# main_V2.net
KiCad netlist of a schematic drawn in EAGLE
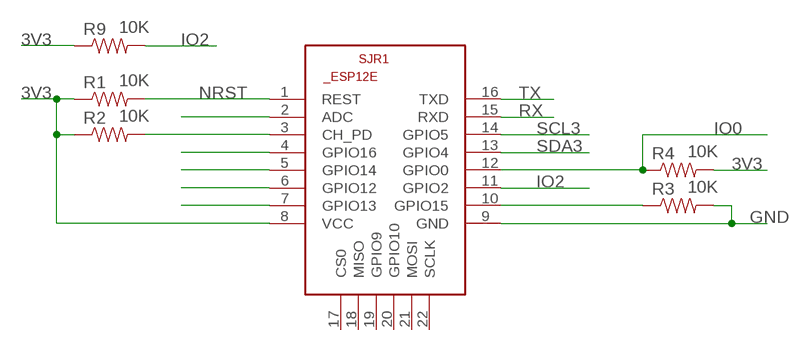
[diagram p0: schematic, sheet 1]
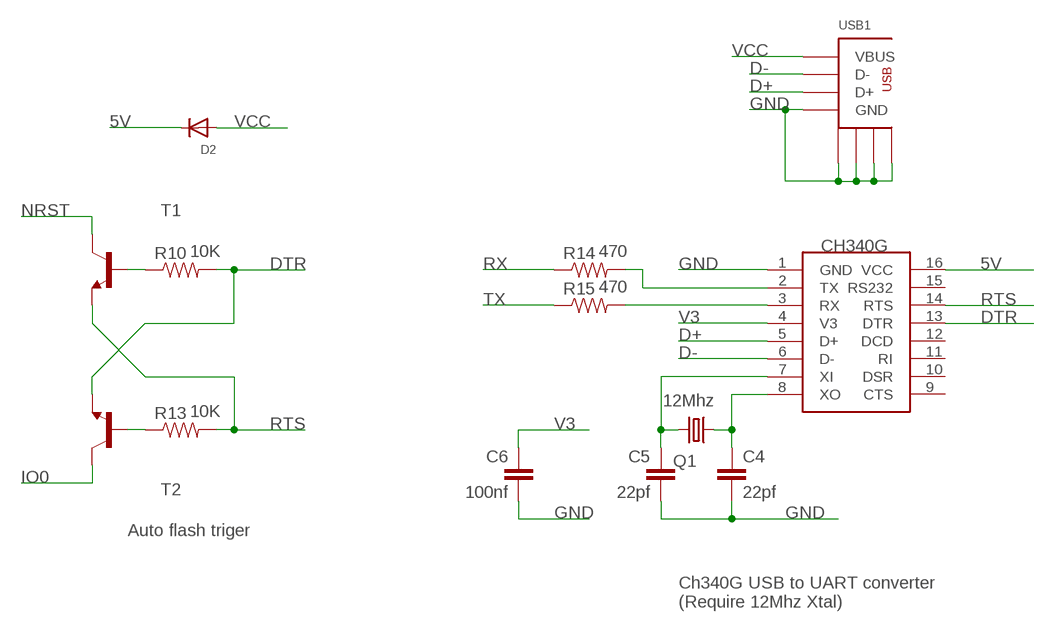
[diagram p1: schematic, sheet 2]
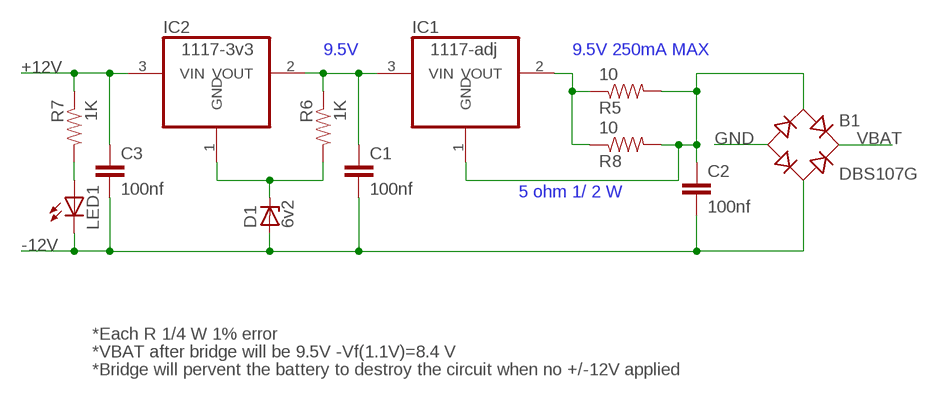
[diagram p2: schematic, sheet 3]
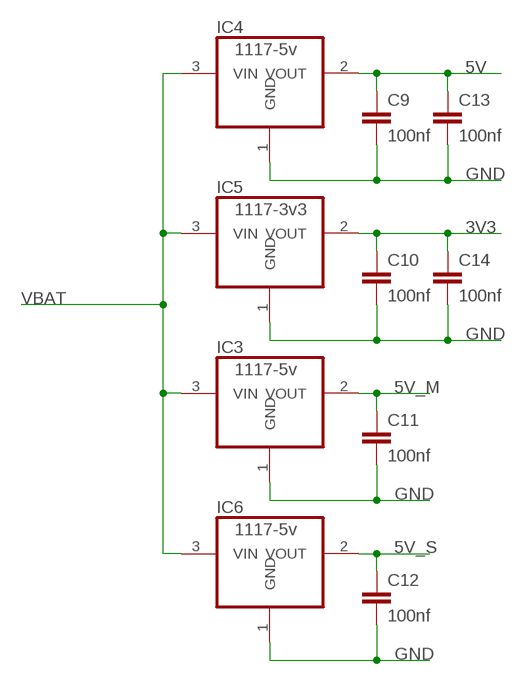
[diagram p3: schematic, sheet 4]
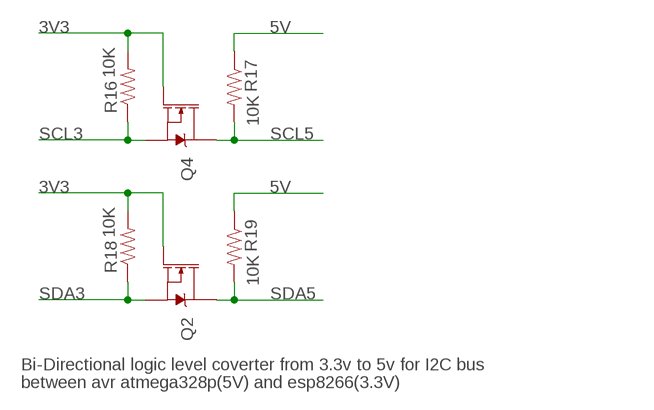
[diagram p4: schematic, sheet 5]
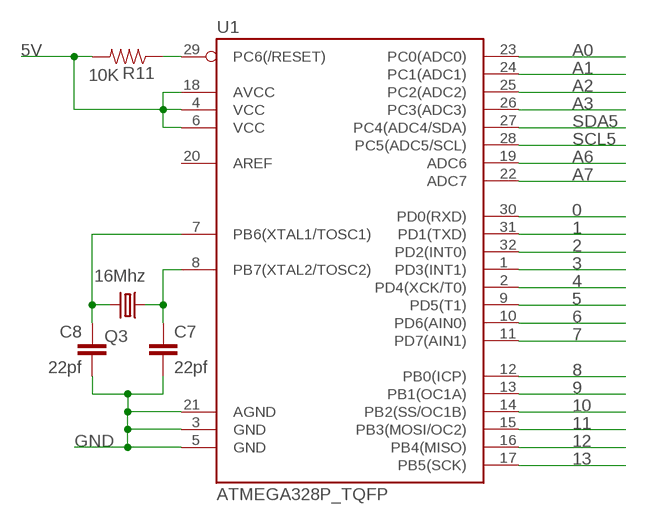
[diagram p5: schematic, sheet 6]
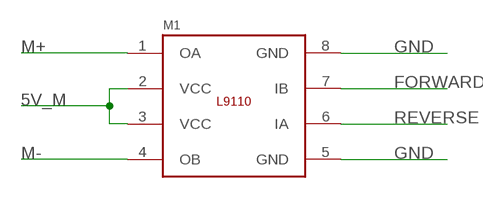
[diagram p6: schematic, sheet 7]

(export (version "E")
  (design (tool "Eeschema 10.0.6"))
  (components
    (comp (ref "C9")
      (value "100nf")
      (footprint "eagle-import:C1206K")
      (libsource (lib "eagle-import") (part "C-EUC1206K"))
    )
    (comp (ref "C10")
      (value "100nf")
      (footprint "eagle-import:C1206K")
      (libsource (lib "eagle-import") (part "C-EUC1206K"))
    )
    (comp (ref "C11")
      (value "100nf")
      (footprint "eagle-import:C1206K")
      (libsource (lib "eagle-import") (part "C-EUC1206K"))
    )
    (comp (ref "C12")
      (value "100nf")
      (footprint "eagle-import:C1206K")
      (libsource (lib "eagle-import") (part "C-EUC1206K"))
    )
    (comp (ref "C13")
      (value "100nf")
      (footprint "eagle-import:C1206K")
      (libsource (lib "eagle-import") (part "C-EUC1206K"))
    )
    (comp (ref "C14")
      (value "100nf")
      (footprint "eagle-import:C1206K")
      (libsource (lib "eagle-import") (part "C-EUC1206K"))
    )
    (comp (ref "IC3")
      (value "1117-5v")
      (footprint "eagle-import:SOT223")
      (fields (field (name "MPN") "REG1117"))
      (libsource (lib "eagle-import") (part "REG1117"))
    )
    (comp (ref "IC4")
      (value "1117-5v")
      (footprint "eagle-import:SOT223")
      (fields (field (name "MPN") "REG1117"))
      (libsource (lib "eagle-import") (part "REG1117"))
    )
    (comp (ref "IC5")
      (value "1117-3v3")
      (footprint "eagle-import:SOT223")
      (fields (field (name "MPN") "REG1117"))
      (libsource (lib "eagle-import") (part "REG1117"))
    )
    (comp (ref "IC6")
      (value "1117-5v")
      (footprint "eagle-import:SOT223")
      (fields (field (name "MPN") "REG1117"))
      (libsource (lib "eagle-import") (part "REG1117"))
    )
    (comp (ref "B1")
      (value "DBS107G")
      (footprint "eagle-import:DBS")
      (libsource (lib "eagle-import") (part "DB?GS107"))
    )
    (comp (ref "C1")
      (value "100nf")
      (footprint "eagle-import:C1206K")
      (libsource (lib "eagle-import") (part "C-EUC1206K"))
    )
    (comp (ref "C2")
      (value "100nf")
      (footprint "eagle-import:C1206K")
      (libsource (lib "eagle-import") (part "C-EUC1206K"))
    )
    (comp (ref "C3")
      (value "100nf")
      (footprint "eagle-import:C1206K")
      (libsource (lib "eagle-import") (part "C-EUC1206K"))
    )
    (comp (ref "D1")
      (value "6v2")
      (footprint "eagle-import:SOT23")
      (libsource (lib "eagle-import") (part "ZENER-DIODESOT23"))
    )
    (comp (ref "IC1")
      (value "1117-adj")
      (footprint "eagle-import:SOT223")
      (fields (field (name "MPN") "REG1117"))
      (libsource (lib "eagle-import") (part "REG1117"))
    )
    (comp (ref "IC2")
      (value "1117-3v3")
      (footprint "eagle-import:SOT223")
      (fields (field (name "MPN") "REG1117"))
      (libsource (lib "eagle-import") (part "REG1117"))
    )
    (comp (ref "LED1")
      (value "LEDSMT1206")
      (footprint "eagle-import:1206")
      (libsource (lib "eagle-import") (part "LEDSMT1206"))
    )
    (comp (ref "R5")
      (value "10")
      (footprint "eagle-import:1206")
      (libsource (lib "eagle-import") (part "RESISTOR1206"))
    )
    (comp (ref "R6")
      (value "1K")
      (footprint "eagle-import:1206")
      (libsource (lib "eagle-import") (part "RESISTOR1206"))
    )
    (comp (ref "R7")
      (value "1K")
      (footprint "eagle-import:1206")
      (libsource (lib "eagle-import") (part "RESISTOR1206"))
    )
    (comp (ref "R8")
      (value "10")
      (footprint "eagle-import:1206")
      (libsource (lib "eagle-import") (part "RESISTOR1206"))
    )
    (comp (ref "M1")
      (value "L9110")
      (footprint "eagle-import:SO8P")
      (libsource (lib "eagle-import") (part "L9110"))
    )
    (comp (ref "C4")
      (value "22pf")
      (footprint "eagle-import:C1206K")
      (libsource (lib "eagle-import") (part "C-EUC1206K"))
    )
    (comp (ref "C5")
      (value "22pf")
      (footprint "eagle-import:C1206K")
      (libsource (lib "eagle-import") (part "C-EUC1206K"))
    )
    (comp (ref "C6")
      (value "100nf")
      (footprint "eagle-import:C1206K")
      (libsource (lib "eagle-import") (part "C-EUC1206K"))
    )
    (comp (ref "D2")
      (value "DIODESMA")
      (footprint "eagle-import:SMADIODE")
      (libsource (lib "eagle-import") (part "DIODESMA"))
    )
    (comp (ref "Q1")
      (value "12Mhz")
      (footprint "eagle-import:CSM-7X-DU")
      (libsource (lib "eagle-import") (part "CSM-7X-DU"))
    )
    (comp (ref "R10")
      (value "10K")
      (footprint "eagle-import:1206")
      (libsource (lib "eagle-import") (part "RESISTOR1206"))
    )
    (comp (ref "R13")
      (value "10K")
      (footprint "eagle-import:1206")
      (libsource (lib "eagle-import") (part "RESISTOR1206"))
    )
    (comp (ref "R14")
      (value "470")
      (footprint "eagle-import:1206")
      (libsource (lib "eagle-import") (part "RESISTOR1206"))
    )
    (comp (ref "R15")
      (value "470")
      (footprint "eagle-import:1206")
      (libsource (lib "eagle-import") (part "RESISTOR1206"))
    )
    (comp (ref "T1")
      (value "MMBT5551LT1-NPN-SOT23-BEC")
      (footprint "eagle-import:SOT23-BEC")
      (libsource (lib "eagle-import") (part "-NPN-SOT23-BECMMBT5551LT1"))
    )
    (comp (ref "T2")
      (value "MMBT5551LT1-NPN-SOT23-BEC")
      (footprint "eagle-import:SOT23-BEC")
      (libsource (lib "eagle-import") (part "-NPN-SOT23-BECMMBT5551LT1"))
    )
    (comp (ref "U$1")
      (value "CH340G")
      (footprint "eagle-import:SOIC16")
      (libsource (lib "eagle-import") (part "CH340G"))
    )
    (comp (ref "USB1")
      (value "USB3MINI")
      (footprint "eagle-import:USB-MB-S")
      (libsource (lib "eagle-import") (part "USB3MINI"))
    )
    (comp (ref "R1")
      (value "10K")
      (footprint "eagle-import:1206")
      (libsource (lib "eagle-import") (part "RESISTOR1206"))
    )
    (comp (ref "R2")
      (value "10K")
      (footprint "eagle-import:1206")
      (libsource (lib "eagle-import") (part "RESISTOR1206"))
    )
    (comp (ref "R3")
      (value "10K")
      (footprint "eagle-import:1206")
      (libsource (lib "eagle-import") (part "RESISTOR1206"))
    )
    (comp (ref "R4")
      (value "10K")
      (footprint "eagle-import:1206")
      (libsource (lib "eagle-import") (part "RESISTOR1206"))
    )
    (comp (ref "R9")
      (value "10K")
      (footprint "eagle-import:1206")
      (libsource (lib "eagle-import") (part "RESISTOR1206"))
    )
    (comp (ref "SJR1")
      (value "ESP8266-12EESP12E")
      (footprint "eagle-import:ESP8266-ESP12E")
      (libsource (lib "eagle-import") (part "ESP8266-12EESP12E"))
    )
    (comp (ref "C7")
      (value "22pf")
      (footprint "eagle-import:C1206K")
      (libsource (lib "eagle-import") (part "C-EUC1206K"))
    )
    (comp (ref "C8")
      (value "22pf")
      (footprint "eagle-import:C1206K")
      (libsource (lib "eagle-import") (part "C-EUC1206K"))
    )
    (comp (ref "Q3")
      (value "16Mhz")
      (footprint "eagle-import:CSM-7X-DU")
      (libsource (lib "eagle-import") (part "CSM-7X-DU"))
    )
    (comp (ref "R11")
      (value "10K")
      (footprint "eagle-import:1206")
      (libsource (lib "eagle-import") (part "RESISTOR1206"))
    )
    (comp (ref "U1")
      (value "ATMEGA328P_TQFP")
      (footprint "eagle-import:TQFP32-08")
      (libsource (lib "eagle-import") (part "ATMEGA328P_TQFP"))
    )
    (comp (ref "Q2")
      (value "MOSFET-NCH-BSS138")
      (footprint "eagle-import:SOT23-3")
      (libsource (lib "eagle-import") (part "MOSFET-NCH-BSS138"))
    )
    (comp (ref "Q4")
      (value "MOSFET-NCH-BSS138")
      (footprint "eagle-import:SOT23-3")
      (libsource (lib "eagle-import") (part "MOSFET-NCH-BSS138"))
    )
    (comp (ref "R16")
      (value "10K")
      (footprint "eagle-import:1206")
      (libsource (lib "eagle-import") (part "RESISTOR1206"))
    )
    (comp (ref "R17")
      (value "10K")
      (footprint "eagle-import:1206")
      (libsource (lib "eagle-import") (part "RESISTOR1206"))
    )
    (comp (ref "R18")
      (value "10K")
      (footprint "eagle-import:1206")
      (libsource (lib "eagle-import") (part "RESISTOR1206"))
    )
    (comp (ref "R19")
      (value "10K")
      (footprint "eagle-import:1206")
      (libsource (lib "eagle-import") (part "RESISTOR1206"))
    )
  )
  (nets
    (net (code "1") (name "+12V") (class "Default")
      (node (ref "C3") (pin "1") (pinfunction "1_1") (pintype "passive"))
      (node (ref "IC2") (pin "3") (pinfunction "VIN_3") (pintype "input"))
      (node (ref "R7") (pin "1") (pinfunction "1_1") (pintype "passive"))
    )
    (net (code "2") (name "-12V") (class "Default")
      (node (ref "B1") (pin "AC2") (pinfunction "AC2_AC2") (pintype "passive"))
      (node (ref "C1") (pin "2") (pinfunction "2_2") (pintype "passive"))
      (node (ref "C2") (pin "2") (pinfunction "2_2") (pintype "passive"))
      (node (ref "C3") (pin "2") (pinfunction "2_2") (pintype "passive"))
      (node (ref "D1") (pin "1") (pinfunction "A_1") (pintype "passive"))
      (node (ref "LED1") (pin "C") (pinfunction "C_C") (pintype "passive"))
    )
    (net (code "3") (name "0") (class "Default")
      (node (ref "U1") (pin "30") (pinfunction "PD0(RXD)_30") (pintype "bidirectional"))
    )
    (net (code "4") (name "1") (class "Default")
      (node (ref "U1") (pin "31") (pinfunction "PD1(TXD)_31") (pintype "bidirectional"))
    )
    (net (code "5") (name "2") (class "Default")
      (node (ref "U1") (pin "32") (pinfunction "PD2(INT0)_32") (pintype "bidirectional"))
    )
    (net (code "6") (name "3") (class "Default")
      (node (ref "U1") (pin "1") (pinfunction "PD3(INT1)_1") (pintype "bidirectional"))
    )
    (net (code "7") (name "3V3") (class "Default")
      (node (ref "C10") (pin "1") (pinfunction "1_1") (pintype "passive"))
      (node (ref "C14") (pin "1") (pinfunction "1_1") (pintype "passive"))
      (node (ref "IC5") (pin "2") (pinfunction "VOUT_2") (pintype "output"))
      (node (ref "Q2") (pin "1") (pinfunction "G_1") (pintype "bidirectional"))
      (node (ref "Q4") (pin "1") (pinfunction "G_1") (pintype "bidirectional"))
      (node (ref "R1") (pin "1") (pinfunction "1_1") (pintype "passive"))
      (node (ref "R16") (pin "2") (pinfunction "2_2") (pintype "passive"))
      (node (ref "R18") (pin "2") (pinfunction "2_2") (pintype "passive"))
      (node (ref "R2") (pin "1") (pinfunction "1_1") (pintype "passive"))
      (node (ref "R4") (pin "2") (pinfunction "2_2") (pintype "passive"))
      (node (ref "R9") (pin "1") (pinfunction "1_1") (pintype "passive"))
      (node (ref "SJR1") (pin "8") (pinfunction "VCC_8") (pintype "bidirectional"))
    )
    (net (code "8") (name "4") (class "Default")
      (node (ref "U1") (pin "2") (pinfunction "PD4(XCK/T0)_2") (pintype "bidirectional"))
    )
    (net (code "9") (name "5") (class "Default")
      (node (ref "U1") (pin "9") (pinfunction "PD5(T1)_9") (pintype "bidirectional"))
    )
    (net (code "10") (name "5V") (class "Default")
      (node (ref "C13") (pin "1") (pinfunction "1_1") (pintype "passive"))
      (node (ref "C9") (pin "1") (pinfunction "1_1") (pintype "passive"))
      (node (ref "D2") (pin "C") (pinfunction "C_C") (pintype "passive"))
      (node (ref "IC4") (pin "2") (pinfunction "VOUT_2") (pintype "output"))
      (node (ref "R11") (pin "2") (pinfunction "2_2") (pintype "passive"))
      (node (ref "R17") (pin "1") (pinfunction "1_1") (pintype "passive"))
      (node (ref "R19") (pin "1") (pinfunction "1_1") (pintype "passive"))
      (node (ref "U$1") (pin "16") (pinfunction "VCC_16") (pintype "bidirectional"))
      (node (ref "U1") (pin "18") (pinfunction "AVCC_18") (pintype "bidirectional"))
      (node (ref "U1") (pin "4") (pinfunction "VCC_4") (pintype "bidirectional"))
      (node (ref "U1") (pin "6") (pinfunction "VCC_6") (pintype "bidirectional"))
    )
    (net (code "11") (name "5V_M") (class "Default")
      (node (ref "C11") (pin "1") (pinfunction "1_1") (pintype "passive"))
      (node (ref "IC3") (pin "2") (pinfunction "VOUT_2") (pintype "output"))
      (node (ref "M1") (pin "2") (pinfunction "VCC_2") (pintype "bidirectional"))
      (node (ref "M1") (pin "3") (pinfunction "VCC_3") (pintype "bidirectional"))
    )
    (net (code "12") (name "5V_S") (class "Default")
      (node (ref "C12") (pin "1") (pinfunction "1_1") (pintype "passive"))
      (node (ref "IC6") (pin "2") (pinfunction "VOUT_2") (pintype "output"))
    )
    (net (code "13") (name "6") (class "Default")
      (node (ref "U1") (pin "10") (pinfunction "PD6(AIN0)_10") (pintype "bidirectional"))
    )
    (net (code "14") (name "7") (class "Default")
      (node (ref "U1") (pin "11") (pinfunction "PD7(AIN1)_11") (pintype "bidirectional"))
    )
    (net (code "15") (name "8") (class "Default")
      (node (ref "U1") (pin "12") (pinfunction "PB0(ICP)_12") (pintype "bidirectional"))
    )
    (net (code "16") (name "9") (class "Default")
      (node (ref "U1") (pin "13") (pinfunction "PB1(OC1A)_13") (pintype "bidirectional"))
    )
    (net (code "17") (name "10") (class "Default")
      (node (ref "U1") (pin "14") (pinfunction "PB2(SS/OC1B)_14") (pintype "bidirectional"))
    )
    (net (code "18") (name "11") (class "Default")
      (node (ref "U1") (pin "15") (pinfunction "PB3(MOSI/OC2)_15") (pintype "bidirectional"))
    )
    (net (code "19") (name "12") (class "Default")
      (node (ref "U1") (pin "16") (pinfunction "PB4(MISO)_16") (pintype "bidirectional"))
    )
    (net (code "20") (name "13") (class "Default")
      (node (ref "U1") (pin "17") (pinfunction "PB5(SCK)_17") (pintype "bidirectional"))
    )
    (net (code "21") (name "A0") (class "Default")
      (node (ref "U1") (pin "23") (pinfunction "PC0(ADC0)_23") (pintype "bidirectional"))
    )
    (net (code "22") (name "A1") (class "Default")
      (node (ref "U1") (pin "24") (pinfunction "PC1(ADC1)_24") (pintype "bidirectional"))
    )
    (net (code "23") (name "A2") (class "Default")
      (node (ref "U1") (pin "25") (pinfunction "PC2(ADC2)_25") (pintype "bidirectional"))
    )
    (net (code "24") (name "A3") (class "Default")
      (node (ref "U1") (pin "26") (pinfunction "PC3(ADC3)_26") (pintype "bidirectional"))
    )
    (net (code "25") (name "A6") (class "Default")
      (node (ref "U1") (pin "19") (pinfunction "ADC6_19") (pintype "bidirectional"))
    )
    (net (code "26") (name "A7") (class "Default")
      (node (ref "U1") (pin "22") (pinfunction "ADC7_22") (pintype "bidirectional"))
    )
    (net (code "27") (name "D+") (class "Default")
      (node (ref "U$1") (pin "5") (pinfunction "D+_5") (pintype "bidirectional"))
      (node (ref "USB1") (pin "D+") (pinfunction "D+_D+") (pintype "bidirectional"))
    )
    (net (code "28") (name "D-") (class "Default")
      (node (ref "U$1") (pin "6") (pinfunction "D-_6") (pintype "bidirectional"))
      (node (ref "USB1") (pin "D-") (pinfunction "D-_D-") (pintype "bidirectional"))
    )
    (net (code "29") (name "DTR") (class "Default")
      (node (ref "R10") (pin "2") (pinfunction "2_2") (pintype "passive"))
      (node (ref "T2") (pin "E") (pinfunction "E_E") (pintype "passive"))
      (node (ref "U$1") (pin "13") (pinfunction "DTR_13") (pintype "bidirectional"))
    )
    (net (code "30") (name "FORWARD") (class "Default")
      (node (ref "M1") (pin "7") (pinfunction "IB_7") (pintype "bidirectional"))
    )
    (net (code "31") (name "GND") (class "Default")
      (node (ref "B1") (pin "-") (pinfunction "-_-") (pintype "passive"))
      (node (ref "C10") (pin "2") (pinfunction "2_2") (pintype "passive"))
      (node (ref "C11") (pin "2") (pinfunction "2_2") (pintype "passive"))
      (node (ref "C12") (pin "2") (pinfunction "2_2") (pintype "passive"))
      (node (ref "C13") (pin "2") (pinfunction "2_2") (pintype "passive"))
      (node (ref "C14") (pin "2") (pinfunction "2_2") (pintype "passive"))
      (node (ref "C4") (pin "2") (pinfunction "2_2") (pintype "passive"))
      (node (ref "C5") (pin "2") (pinfunction "2_2") (pintype "passive"))
      (node (ref "C6") (pin "2") (pinfunction "2_2") (pintype "passive"))
      (node (ref "C7") (pin "2") (pinfunction "2_2") (pintype "passive"))
      (node (ref "C8") (pin "2") (pinfunction "2_2") (pintype "passive"))
      (node (ref "C9") (pin "2") (pinfunction "2_2") (pintype "passive"))
      (node (ref "IC3") (pin "1") (pinfunction "GND_1") (pintype "power_in"))
      (node (ref "IC4") (pin "1") (pinfunction "GND_1") (pintype "power_in"))
      (node (ref "IC5") (pin "1") (pinfunction "GND_1") (pintype "power_in"))
      (node (ref "IC6") (pin "1") (pinfunction "GND_1") (pintype "power_in"))
      (node (ref "M1") (pin "5") (pinfunction "GND_5") (pintype "bidirectional"))
      (node (ref "M1") (pin "8") (pinfunction "GND_8") (pintype "bidirectional"))
      (node (ref "R3") (pin "2") (pinfunction "2_2") (pintype "passive"))
      (node (ref "SJR1") (pin "9") (pinfunction "GND_9") (pintype "bidirectional"))
      (node (ref "U$1") (pin "1") (pinfunction "GND_1") (pintype "bidirectional"))
      (node (ref "U1") (pin "21") (pinfunction "AGND_21") (pintype "bidirectional"))
      (node (ref "U1") (pin "3") (pinfunction "GND_3") (pintype "bidirectional"))
      (node (ref "U1") (pin "5") (pinfunction "GND_5") (pintype "bidirectional"))
      (node (ref "USB1") (pin "GND") (pinfunction "GND_GND") (pintype "bidirectional"))
      (node (ref "USB1") (pin "P$1") (pinfunction "GND_P$1") (pintype "bidirectional"))
      (node (ref "USB1") (pin "P$2") (pinfunction "GND_P$2") (pintype "bidirectional"))
      (node (ref "USB1") (pin "P$3") (pinfunction "GND_P$3") (pintype "bidirectional"))
      (node (ref "USB1") (pin "P$4") (pinfunction "GND_P$4") (pintype "bidirectional"))
    )
    (net (code "32") (name "IO0") (class "Default")
      (node (ref "R4") (pin "1") (pinfunction "1_1") (pintype "passive"))
      (node (ref "SJR1") (pin "12") (pinfunction "GPIO0_12") (pintype "bidirectional"))
      (node (ref "T2") (pin "C") (pinfunction "C_C") (pintype "passive"))
    )
    (net (code "33") (name "IO2") (class "Default")
      (node (ref "R9") (pin "2") (pinfunction "2_2") (pintype "passive"))
      (node (ref "SJR1") (pin "11") (pinfunction "GPIO2_11") (pintype "bidirectional"))
    )
    (net (code "34") (name "M+") (class "Default")
      (node (ref "M1") (pin "1") (pinfunction "OA_1") (pintype "bidirectional"))
    )
    (net (code "35") (name "M-") (class "Default")
      (node (ref "M1") (pin "4") (pinfunction "OB_4") (pintype "bidirectional"))
    )
    (net (code "36") (name "NRST") (class "Default")
      (node (ref "R1") (pin "2") (pinfunction "2_2") (pintype "passive"))
      (node (ref "SJR1") (pin "1") (pinfunction "REST_1") (pintype "bidirectional"))
      (node (ref "T1") (pin "C") (pinfunction "C_C") (pintype "passive"))
    )
    (net (code "37") (name "Net-(D1-C)") (class "Default")
      (node (ref "D1") (pin "3") (pinfunction "C_3") (pintype "passive"))
      (node (ref "IC2") (pin "1") (pinfunction "GND_1") (pintype "power_in"))
      (node (ref "R6") (pin "2") (pinfunction "2_2") (pintype "passive"))
    )
    (net (code "38") (name "Net-(IC1-GND)") (class "Default")
      (node (ref "B1") (pin "AC1") (pinfunction "AC1_AC1") (pintype "passive"))
      (node (ref "C2") (pin "1") (pinfunction "1_1") (pintype "passive"))
      (node (ref "IC1") (pin "1") (pinfunction "GND_1") (pintype "power_in"))
      (node (ref "R5") (pin "2") (pinfunction "2_2") (pintype "passive"))
      (node (ref "R8") (pin "2") (pinfunction "2_2") (pintype "passive"))
    )
    (net (code "39") (name "Net-(IC1-VIN)") (class "Default")
      (node (ref "C1") (pin "1") (pinfunction "1_1") (pintype "passive"))
      (node (ref "IC1") (pin "3") (pinfunction "VIN_3") (pintype "input"))
      (node (ref "IC2") (pin "2") (pinfunction "VOUT_2") (pintype "output"))
      (node (ref "R6") (pin "1") (pinfunction "1_1") (pintype "passive"))
    )
    (net (code "40") (name "Net-(IC1-VOUT)") (class "Default")
      (node (ref "IC1") (pin "2") (pinfunction "VOUT_2") (pintype "output"))
      (node (ref "R5") (pin "1") (pinfunction "1_1") (pintype "passive"))
      (node (ref "R8") (pin "1") (pinfunction "1_1") (pintype "passive"))
    )
    (net (code "41") (name "Net-(LED1-PadA)") (class "Default")
      (node (ref "LED1") (pin "A") (pinfunction "A_A") (pintype "passive"))
      (node (ref "R7") (pin "2") (pinfunction "2_2") (pintype "passive"))
    )
    (net (code "42") (name "Net-(R10-Pad1)") (class "Default")
      (node (ref "R10") (pin "1") (pinfunction "1_1") (pintype "passive"))
      (node (ref "T1") (pin "B") (pinfunction "B_B") (pintype "passive"))
    )
    (net (code "43") (name "Net-(R13-Pad1)") (class "Default")
      (node (ref "R13") (pin "1") (pinfunction "1_1") (pintype "passive"))
      (node (ref "T2") (pin "B") (pinfunction "B_B") (pintype "passive"))
    )
    (net (code "44") (name "Net-(SJR1-CH_PD)") (class "Default")
      (node (ref "R2") (pin "2") (pinfunction "2_2") (pintype "passive"))
      (node (ref "SJR1") (pin "3") (pinfunction "CH_PD_3") (pintype "bidirectional"))
    )
    (net (code "45") (name "Net-(SJR1-GPIO15)") (class "Default")
      (node (ref "R3") (pin "1") (pinfunction "1_1") (pintype "passive"))
      (node (ref "SJR1") (pin "10") (pinfunction "GPIO15_10") (pintype "bidirectional"))
    )
    (net (code "46") (name "Net-(U$1-RX)") (class "Default")
      (node (ref "R15") (pin "2") (pinfunction "2_2") (pintype "passive"))
      (node (ref "U$1") (pin "3") (pinfunction "RX_3") (pintype "bidirectional"))
    )
    (net (code "47") (name "Net-(U$1-TX)") (class "Default")
      (node (ref "R14") (pin "2") (pinfunction "2_2") (pintype "passive"))
      (node (ref "U$1") (pin "2") (pinfunction "TX_2") (pintype "bidirectional"))
    )
    (net (code "48") (name "Net-(U$1-XI)") (class "Default")
      (node (ref "C5") (pin "1") (pinfunction "1_1") (pintype "passive"))
      (node (ref "Q1") (pin "2") (pinfunction "2_2") (pintype "passive"))
      (node (ref "U$1") (pin "7") (pinfunction "XI_7") (pintype "bidirectional"))
    )
    (net (code "49") (name "Net-(U$1-XO)") (class "Default")
      (node (ref "C4") (pin "1") (pinfunction "1_1") (pintype "passive"))
      (node (ref "Q1") (pin "1") (pinfunction "1_1") (pintype "passive"))
      (node (ref "U$1") (pin "8") (pinfunction "XO_8") (pintype "bidirectional"))
    )
    (net (code "50") (name "Net-(U1-PB6(XTAL1{slash}TOSC1))") (class "Default")
      (node (ref "C8") (pin "1") (pinfunction "1_1") (pintype "passive"))
      (node (ref "Q3") (pin "2") (pinfunction "2_2") (pintype "passive"))
      (node (ref "U1") (pin "7") (pinfunction "PB6(XTAL1/TOSC1)_7") (pintype "bidirectional"))
    )
    (net (code "51") (name "Net-(U1-PB7(XTAL2{slash}TOSC2))") (class "Default")
      (node (ref "C7") (pin "1") (pinfunction "1_1") (pintype "passive"))
      (node (ref "Q3") (pin "1") (pinfunction "1_1") (pintype "passive"))
      (node (ref "U1") (pin "8") (pinfunction "PB7(XTAL2/TOSC2)_8") (pintype "bidirectional"))
    )
    (net (code "52") (name "Net-(U1-PC6({slash}RESET))") (class "Default")
      (node (ref "R11") (pin "1") (pinfunction "1_1") (pintype "passive"))
      (node (ref "U1") (pin "29") (pinfunction "PC6(/RESET)_29") (pintype "bidirectional"))
    )
    (net (code "53") (name "REVERSE") (class "Default")
      (node (ref "M1") (pin "6") (pinfunction "IA_6") (pintype "bidirectional"))
    )
    (net (code "54") (name "RTS") (class "Default")
      (node (ref "R13") (pin "2") (pinfunction "2_2") (pintype "passive"))
      (node (ref "T1") (pin "E") (pinfunction "E_E") (pintype "passive"))
      (node (ref "U$1") (pin "14") (pinfunction "RTS_14") (pintype "bidirectional"))
    )
    (net (code "55") (name "RX") (class "Default")
      (node (ref "R14") (pin "1") (pinfunction "1_1") (pintype "passive"))
      (node (ref "SJR1") (pin "15") (pinfunction "RXD_15") (pintype "bidirectional"))
    )
    (net (code "56") (name "SCL3") (class "Default")
      (node (ref "Q4") (pin "2") (pinfunction "S_2") (pintype "bidirectional"))
      (node (ref "R16") (pin "1") (pinfunction "1_1") (pintype "passive"))
      (node (ref "SJR1") (pin "14") (pinfunction "GPIO5_14") (pintype "bidirectional"))
    )
    (net (code "57") (name "SCL5") (class "Default")
      (node (ref "Q4") (pin "3") (pinfunction "D_3") (pintype "bidirectional"))
      (node (ref "R17") (pin "2") (pinfunction "2_2") (pintype "passive"))
      (node (ref "U1") (pin "28") (pinfunction "PC5(ADC5/SCL)_28") (pintype "bidirectional"))
    )
    (net (code "58") (name "SDA3") (class "Default")
      (node (ref "Q2") (pin "2") (pinfunction "S_2") (pintype "bidirectional"))
      (node (ref "R18") (pin "1") (pinfunction "1_1") (pintype "passive"))
      (node (ref "SJR1") (pin "13") (pinfunction "GPIO4_13") (pintype "bidirectional"))
    )
    (net (code "59") (name "SDA5") (class "Default")
      (node (ref "Q2") (pin "3") (pinfunction "D_3") (pintype "bidirectional"))
      (node (ref "R19") (pin "2") (pinfunction "2_2") (pintype "passive"))
      (node (ref "U1") (pin "27") (pinfunction "PC4(ADC4/SDA)_27") (pintype "bidirectional"))
    )
    (net (code "60") (name "TX") (class "Default")
      (node (ref "R15") (pin "1") (pinfunction "1_1") (pintype "passive"))
      (node (ref "SJR1") (pin "16") (pinfunction "TXD_16") (pintype "bidirectional"))
    )
    (net (code "61") (name "V3") (class "Default")
      (node (ref "C6") (pin "1") (pinfunction "1_1") (pintype "passive"))
      (node (ref "U$1") (pin "4") (pinfunction "V3_4") (pintype "bidirectional"))
    )
    (net (code "62") (name "VBAT") (class "Default")
      (node (ref "B1") (pin "+") (pinfunction "+_+") (pintype "passive"))
      (node (ref "IC3") (pin "3") (pinfunction "VIN_3") (pintype "input"))
      (node (ref "IC4") (pin "3") (pinfunction "VIN_3") (pintype "input"))
      (node (ref "IC5") (pin "3") (pinfunction "VIN_3") (pintype "input"))
      (node (ref "IC6") (pin "3") (pinfunction "VIN_3") (pintype "input"))
    )
    (net (code "63") (name "VCC") (class "Default")
      (node (ref "D2") (pin "A") (pinfunction "A_A") (pintype "passive"))
      (node (ref "USB1") (pin "VBUS") (pinfunction "VBUS_VBUS") (pintype "bidirectional"))
    )
    (net (code "64") (name "unconnected-(SJR1-ADC-Pad2)") (class "Default")
      (node (ref "SJR1") (pin "2") (pinfunction "ADC_2") (pintype "bidirectional"))
    )
    (net (code "65") (name "unconnected-(SJR1-CS0-Pad17)") (class "Default")
      (node (ref "SJR1") (pin "17") (pinfunction "CS0_17") (pintype "bidirectional"))
    )
    (net (code "66") (name "unconnected-(SJR1-GPIO9-Pad19)") (class "Default")
      (node (ref "SJR1") (pin "19") (pinfunction "GPIO9_19") (pintype "bidirectional"))
    )
    (net (code "67") (name "unconnected-(SJR1-GPIO10-Pad20)") (class "Default")
      (node (ref "SJR1") (pin "20") (pinfunction "GPIO10_20") (pintype "bidirectional"))
    )
    (net (code "68") (name "unconnected-(SJR1-GPIO12-Pad6)") (class "Default")
      (node (ref "SJR1") (pin "6") (pinfunction "GPIO12_6") (pintype "bidirectional"))
    )
    (net (code "69") (name "unconnected-(SJR1-GPIO13-Pad7)") (class "Default")
      (node (ref "SJR1") (pin "7") (pinfunction "GPIO13_7") (pintype "bidirectional"))
    )
    (net (code "70") (name "unconnected-(SJR1-GPIO14-Pad5)") (class "Default")
      (node (ref "SJR1") (pin "5") (pinfunction "GPIO14_5") (pintype "bidirectional"))
    )
    (net (code "71") (name "unconnected-(SJR1-GPIO16-Pad4)") (class "Default")
      (node (ref "SJR1") (pin "4") (pinfunction "GPIO16_4") (pintype "bidirectional"))
    )
    (net (code "72") (name "unconnected-(SJR1-MISO-Pad18)") (class "Default")
      (node (ref "SJR1") (pin "18") (pinfunction "MISO_18") (pintype "bidirectional"))
    )
    (net (code "73") (name "unconnected-(SJR1-MOSI-Pad21)") (class "Default")
      (node (ref "SJR1") (pin "21") (pinfunction "MOSI_21") (pintype "bidirectional"))
    )
    (net (code "74") (name "unconnected-(SJR1-SCLK-Pad22)") (class "Default")
      (node (ref "SJR1") (pin "22") (pinfunction "SCLK_22") (pintype "bidirectional"))
    )
    (net (code "75") (name "unconnected-(U$1-CTS-Pad9)") (class "Default")
      (node (ref "U$1") (pin "9") (pinfunction "CTS_9") (pintype "bidirectional"))
    )
    (net (code "76") (name "unconnected-(U$1-DCD-Pad12)") (class "Default")
      (node (ref "U$1") (pin "12") (pinfunction "DCD_12") (pintype "bidirectional"))
    )
    (net (code "77") (name "unconnected-(U$1-DSR-Pad10)") (class "Default")
      (node (ref "U$1") (pin "10") (pinfunction "DSR_10") (pintype "bidirectional"))
    )
    (net (code "78") (name "unconnected-(U$1-RI-Pad11)") (class "Default")
      (node (ref "U$1") (pin "11") (pinfunction "RI_11") (pintype "bidirectional"))
    )
    (net (code "79") (name "unconnected-(U$1-RS232-Pad15)") (class "Default")
      (node (ref "U$1") (pin "15") (pinfunction "RS232_15") (pintype "bidirectional"))
    )
    (net (code "80") (name "unconnected-(U1-AREF-Pad20)") (class "Default")
      (node (ref "U1") (pin "20") (pinfunction "AREF_20") (pintype "bidirectional"))
    )
  )
)
